# prelab8.net
KiCad netlist of a schematic drawn in Altium Designer
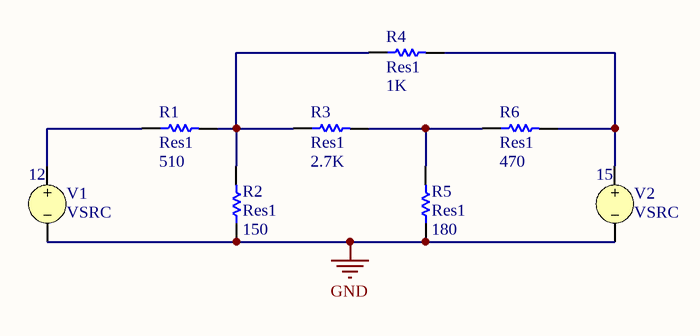
[diagram p0: prelab8.SchDoc]

(export (version "E")
  (design (tool "Eeschema 10.0.6"))
  (components
    (comp (ref "R1")
      (value "Res1")
      (footprint "AXIAL-0.3")
      (description "Resistor")
      (fields (field (name "ALTIUM_VALUE") "510") (field (name "PUBLISHER") "Altium Limited"))
      (libsource (lib "Miscellaneous Devices") (part "Res1"))
    )
    (comp (ref "R2")
      (value "Res1")
      (footprint "AXIAL-0.3")
      (description "Resistor")
      (fields (field (name "ALTIUM_VALUE") "150") (field (name "PUBLISHER") "Altium Limited"))
      (libsource (lib "Miscellaneous Devices") (part "Res1"))
    )
    (comp (ref "R3")
      (value "Res1")
      (footprint "AXIAL-0.3")
      (description "Resistor")
      (fields (field (name "ALTIUM_VALUE") "2.7K") (field (name "PUBLISHER") "Altium Limited"))
      (libsource (lib "Miscellaneous Devices") (part "Res1"))
    )
    (comp (ref "R4")
      (value "Res1")
      (footprint "AXIAL-0.3")
      (description "Resistor")
      (fields (field (name "ALTIUM_VALUE") "1K") (field (name "PUBLISHER") "Altium Limited"))
      (libsource (lib "Miscellaneous Devices") (part "Res1"))
    )
    (comp (ref "R5")
      (value "Res1")
      (footprint "AXIAL-0.3")
      (description "Resistor")
      (fields (field (name "ALTIUM_VALUE") "180") (field (name "PUBLISHER") "Altium Limited"))
      (libsource (lib "Miscellaneous Devices") (part "Res1"))
    )
    (comp (ref "R6")
      (value "Res1")
      (footprint "AXIAL-0.3")
      (description "Resistor")
      (fields (field (name "ALTIUM_VALUE") "470") (field (name "PUBLISHER") "Altium Limited"))
      (libsource (lib "Miscellaneous Devices") (part "Res1"))
    )
    (comp (ref "V1")
      (value "VSRC")
      (description "Voltage Source")
      (fields (field (name "ALTIUM_VALUE") "12") (field (name "PUBLISHER") "Altium Limited"))
      (libsource (lib "Simulation Sources") (part "VSRC"))
    )
    (comp (ref "V2")
      (value "VSRC")
      (description "Voltage Source")
      (fields (field (name "ALTIUM_VALUE") "15") (field (name "PUBLISHER") "Altium Limited"))
      (libsource (lib "Simulation Sources") (part "VSRC"))
    )
  )
  (nets
    (net (code "1") (name "GND") (class "Default")
      (node (ref "R2") (pin "1") (pinfunction "1_1") (pintype "passive"))
      (node (ref "R5") (pin "1") (pinfunction "1_1") (pintype "passive"))
      (node (ref "V1") (pin "2") (pinfunction "2_2") (pintype "passive"))
      (node (ref "V2") (pin "2") (pinfunction "2_2") (pintype "passive"))
    )
    (net (code "2") (name "Net-(R1-Pad1)") (class "Default")
      (node (ref "R1") (pin "1") (pinfunction "1_1") (pintype "passive"))
      (node (ref "V1") (pin "1") (pinfunction "1_1") (pintype "passive"))
    )
    (net (code "3") (name "Net-(R1-Pad2)") (class "Default")
      (node (ref "R1") (pin "2") (pinfunction "2_2") (pintype "passive"))
      (node (ref "R2") (pin "2") (pinfunction "2_2") (pintype "passive"))
      (node (ref "R3") (pin "1") (pinfunction "1_1") (pintype "passive"))
      (node (ref "R4") (pin "1") (pinfunction "1_1") (pintype "passive"))
    )
    (net (code "4") (name "Net-(R3-Pad2)") (class "Default")
      (node (ref "R3") (pin "2") (pinfunction "2_2") (pintype "passive"))
      (node (ref "R5") (pin "2") (pinfunction "2_2") (pintype "passive"))
      (node (ref "R6") (pin "1") (pinfunction "1_1") (pintype "passive"))
    )
    (net (code "5") (name "Net-(R4-Pad2)") (class "Default")
      (node (ref "R4") (pin "2") (pinfunction "2_2") (pintype "passive"))
      (node (ref "R6") (pin "2") (pinfunction "2_2") (pintype "passive"))
      (node (ref "V2") (pin "1") (pinfunction "1_1") (pintype "passive"))
    )
  )
)
